# 7ch_op_amp_board_v42.net
KiCad netlist of a schematic drawn in EAGLE
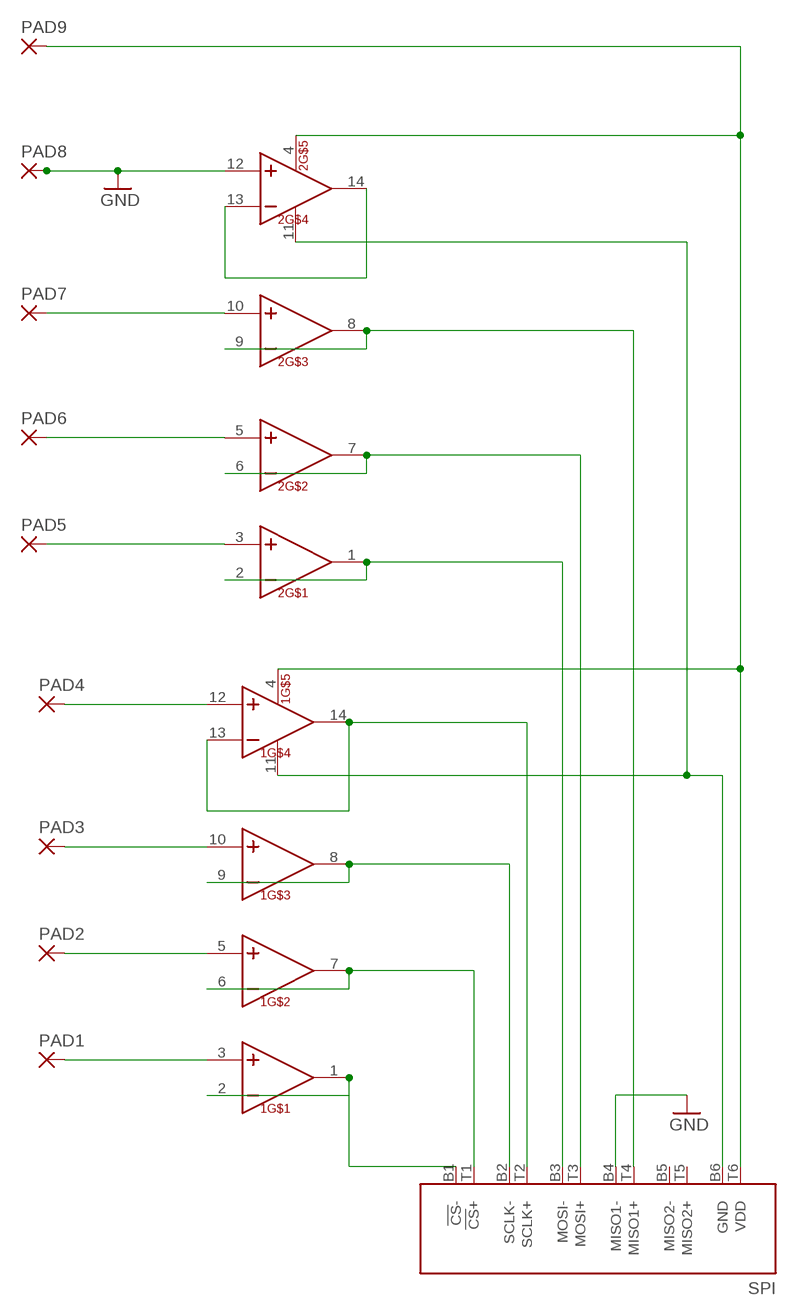
[diagram p0: schematic, sheet 1]

(export (version "E")
  (design (tool "Eeschema 10.0.6"))
  (components
    (comp (ref "1")
      (value "TL074-TSSOP")
      (footprint "eagle-import:TSSOP14")
      (libsource (lib "eagle-import") (part "TL074-TSSOP"))
    )
    (comp (ref "2")
      (value "TL074-TSSOP")
      (footprint "eagle-import:TSSOP14")
      (libsource (lib "eagle-import") (part "TL074-TSSOP"))
    )
    (comp (ref "PAD1")
      (value "1,6/0,9")
      (footprint "eagle-import:1,6_0,9")
      (libsource (lib "eagle-import") (part "1,6/0,9"))
    )
    (comp (ref "PAD2")
      (value "1,6/0,9")
      (footprint "eagle-import:1,6_0,9")
      (libsource (lib "eagle-import") (part "1,6/0,9"))
    )
    (comp (ref "PAD3")
      (value "1,6/0,9")
      (footprint "eagle-import:1,6_0,9")
      (libsource (lib "eagle-import") (part "1,6/0,9"))
    )
    (comp (ref "PAD4")
      (value "1,6/0,9")
      (footprint "eagle-import:1,6_0,9")
      (libsource (lib "eagle-import") (part "1,6/0,9"))
    )
    (comp (ref "PAD5")
      (value "1,6/0,9")
      (footprint "eagle-import:1,6_0,9")
      (libsource (lib "eagle-import") (part "1,6/0,9"))
    )
    (comp (ref "PAD6")
      (value "1,6/0,9")
      (footprint "eagle-import:1,6_0,9")
      (libsource (lib "eagle-import") (part "1,6/0,9"))
    )
    (comp (ref "PAD7")
      (value "1,6/0,9")
      (footprint "eagle-import:1,6_0,9")
      (libsource (lib "eagle-import") (part "1,6/0,9"))
    )
    (comp (ref "PAD8")
      (value "1,6/0,9")
      (footprint "eagle-import:1,6_0,9")
      (libsource (lib "eagle-import") (part "1,6/0,9"))
    )
    (comp (ref "PAD9")
      (value "1,6/0,9")
      (footprint "eagle-import:1,6_0,9")
      (libsource (lib "eagle-import") (part "1,6/0,9"))
    )
    (comp (ref "SPI")
      (value "RHD2000-CABLE-AMP-SIDE")
      (footprint "eagle-import:OMNETICS_PZN-12-AA")
      (libsource (lib "eagle-import") (part "RHD2000-CABLE-AMP-SIDE"))
    )
  )
  (nets
    (net (code "1") (name "GND") (class "Default")
      (node (ref "2") (pin "12") (pinfunction "IN+_12") (pintype "input"))
      (node (ref "PAD8") (pin "1") (pinfunction "P_1") (pintype "passive"))
      (node (ref "SPI") (pin "B4") (pinfunction "MISO1-_B4") (pintype "bidirectional"))
    )
    (net (code "2") (name "Net-(1A-IN+)") (class "Default")
      (node (ref "1") (pin "3") (pinfunction "IN+_3") (pintype "input"))
      (node (ref "PAD1") (pin "1") (pinfunction "P_1") (pintype "passive"))
    )
    (net (code "3") (name "Net-(1A-IN-)") (class "Default")
      (node (ref "1") (pin "1") (pinfunction "OUT_1") (pintype "output"))
      (node (ref "1") (pin "2") (pinfunction "IN-_2") (pintype "input"))
      (node (ref "SPI") (pin "B1") (pinfunction "~{CS}-_B1") (pintype "bidirectional"))
    )
    (net (code "4") (name "Net-(1B-IN+)") (class "Default")
      (node (ref "1") (pin "5") (pinfunction "IN+_5") (pintype "input"))
      (node (ref "PAD2") (pin "1") (pinfunction "P_1") (pintype "passive"))
    )
    (net (code "5") (name "Net-(1B-IN-)") (class "Default")
      (node (ref "1") (pin "6") (pinfunction "IN-_6") (pintype "input"))
      (node (ref "1") (pin "7") (pinfunction "OUT_7") (pintype "output"))
      (node (ref "SPI") (pin "T1") (pinfunction "~{CS}+_T1") (pintype "bidirectional"))
    )
    (net (code "6") (name "Net-(1C-IN+)") (class "Default")
      (node (ref "1") (pin "10") (pinfunction "IN+_10") (pintype "input"))
      (node (ref "PAD3") (pin "1") (pinfunction "P_1") (pintype "passive"))
    )
    (net (code "7") (name "Net-(1C-IN-)") (class "Default")
      (node (ref "1") (pin "8") (pinfunction "OUT_8") (pintype "output"))
      (node (ref "1") (pin "9") (pinfunction "IN-_9") (pintype "input"))
      (node (ref "SPI") (pin "B2") (pinfunction "SCLK-_B2") (pintype "bidirectional"))
    )
    (net (code "8") (name "Net-(1D-IN+)") (class "Default")
      (node (ref "1") (pin "12") (pinfunction "IN+_12") (pintype "input"))
      (node (ref "PAD4") (pin "1") (pinfunction "P_1") (pintype "passive"))
    )
    (net (code "9") (name "Net-(1D-IN-)") (class "Default")
      (node (ref "1") (pin "13") (pinfunction "IN-_13") (pintype "input"))
      (node (ref "1") (pin "14") (pinfunction "OUT_14") (pintype "output"))
      (node (ref "SPI") (pin "T2") (pinfunction "SCLK+_T2") (pintype "bidirectional"))
    )
    (net (code "10") (name "Net-(1E-VCC+)") (class "Default")
      (node (ref "1") (pin "4") (pinfunction "VCC+_4") (pintype "power_in"))
      (node (ref "2") (pin "4") (pinfunction "VCC+_4") (pintype "power_in"))
      (node (ref "PAD9") (pin "1") (pinfunction "P_1") (pintype "passive"))
      (node (ref "SPI") (pin "T6") (pinfunction "VDD_T6") (pintype "bidirectional"))
    )
    (net (code "11") (name "Net-(1E-VCC-)") (class "Default")
      (node (ref "1") (pin "11") (pinfunction "VCC-_11") (pintype "power_in"))
      (node (ref "2") (pin "11") (pinfunction "VCC-_11") (pintype "power_in"))
      (node (ref "SPI") (pin "B6") (pinfunction "GND_B6") (pintype "power_in"))
    )
    (net (code "12") (name "Net-(2A-IN+)") (class "Default")
      (node (ref "2") (pin "3") (pinfunction "IN+_3") (pintype "input"))
      (node (ref "PAD5") (pin "1") (pinfunction "P_1") (pintype "passive"))
    )
    (net (code "13") (name "Net-(2A-IN-)") (class "Default")
      (node (ref "2") (pin "1") (pinfunction "OUT_1") (pintype "output"))
      (node (ref "2") (pin "2") (pinfunction "IN-_2") (pintype "input"))
      (node (ref "SPI") (pin "B3") (pinfunction "MOSI-_B3") (pintype "bidirectional"))
    )
    (net (code "14") (name "Net-(2B-IN+)") (class "Default")
      (node (ref "2") (pin "5") (pinfunction "IN+_5") (pintype "input"))
      (node (ref "PAD6") (pin "1") (pinfunction "P_1") (pintype "passive"))
    )
    (net (code "15") (name "Net-(2B-IN-)") (class "Default")
      (node (ref "2") (pin "6") (pinfunction "IN-_6") (pintype "input"))
      (node (ref "2") (pin "7") (pinfunction "OUT_7") (pintype "output"))
      (node (ref "SPI") (pin "T3") (pinfunction "MOSI+_T3") (pintype "bidirectional"))
    )
    (net (code "16") (name "Net-(2C-IN+)") (class "Default")
      (node (ref "2") (pin "10") (pinfunction "IN+_10") (pintype "input"))
      (node (ref "PAD7") (pin "1") (pinfunction "P_1") (pintype "passive"))
    )
    (net (code "17") (name "Net-(2C-IN-)") (class "Default")
      (node (ref "2") (pin "8") (pinfunction "OUT_8") (pintype "output"))
      (node (ref "2") (pin "9") (pinfunction "IN-_9") (pintype "input"))
      (node (ref "SPI") (pin "T4") (pinfunction "MISO1+_T4") (pintype "bidirectional"))
    )
    (net (code "18") (name "Net-(2D-IN-)") (class "Default")
      (node (ref "2") (pin "13") (pinfunction "IN-_13") (pintype "input"))
      (node (ref "2") (pin "14") (pinfunction "OUT_14") (pintype "output"))
    )
    (net (code "19") (name "unconnected-(SPI-MISO2+-PadT5)") (class "Default")
      (node (ref "SPI") (pin "T5") (pinfunction "MISO2+_T5") (pintype "bidirectional"))
    )
    (net (code "20") (name "unconnected-(SPI-MISO2--PadB5)") (class "Default")
      (node (ref "SPI") (pin "B5") (pinfunction "MISO2-_B5") (pintype "bidirectional"))
    )
  )
)
